# Reefwing-NFC-Card-RevC.net
KiCad netlist of a schematic drawn in EasyEDA
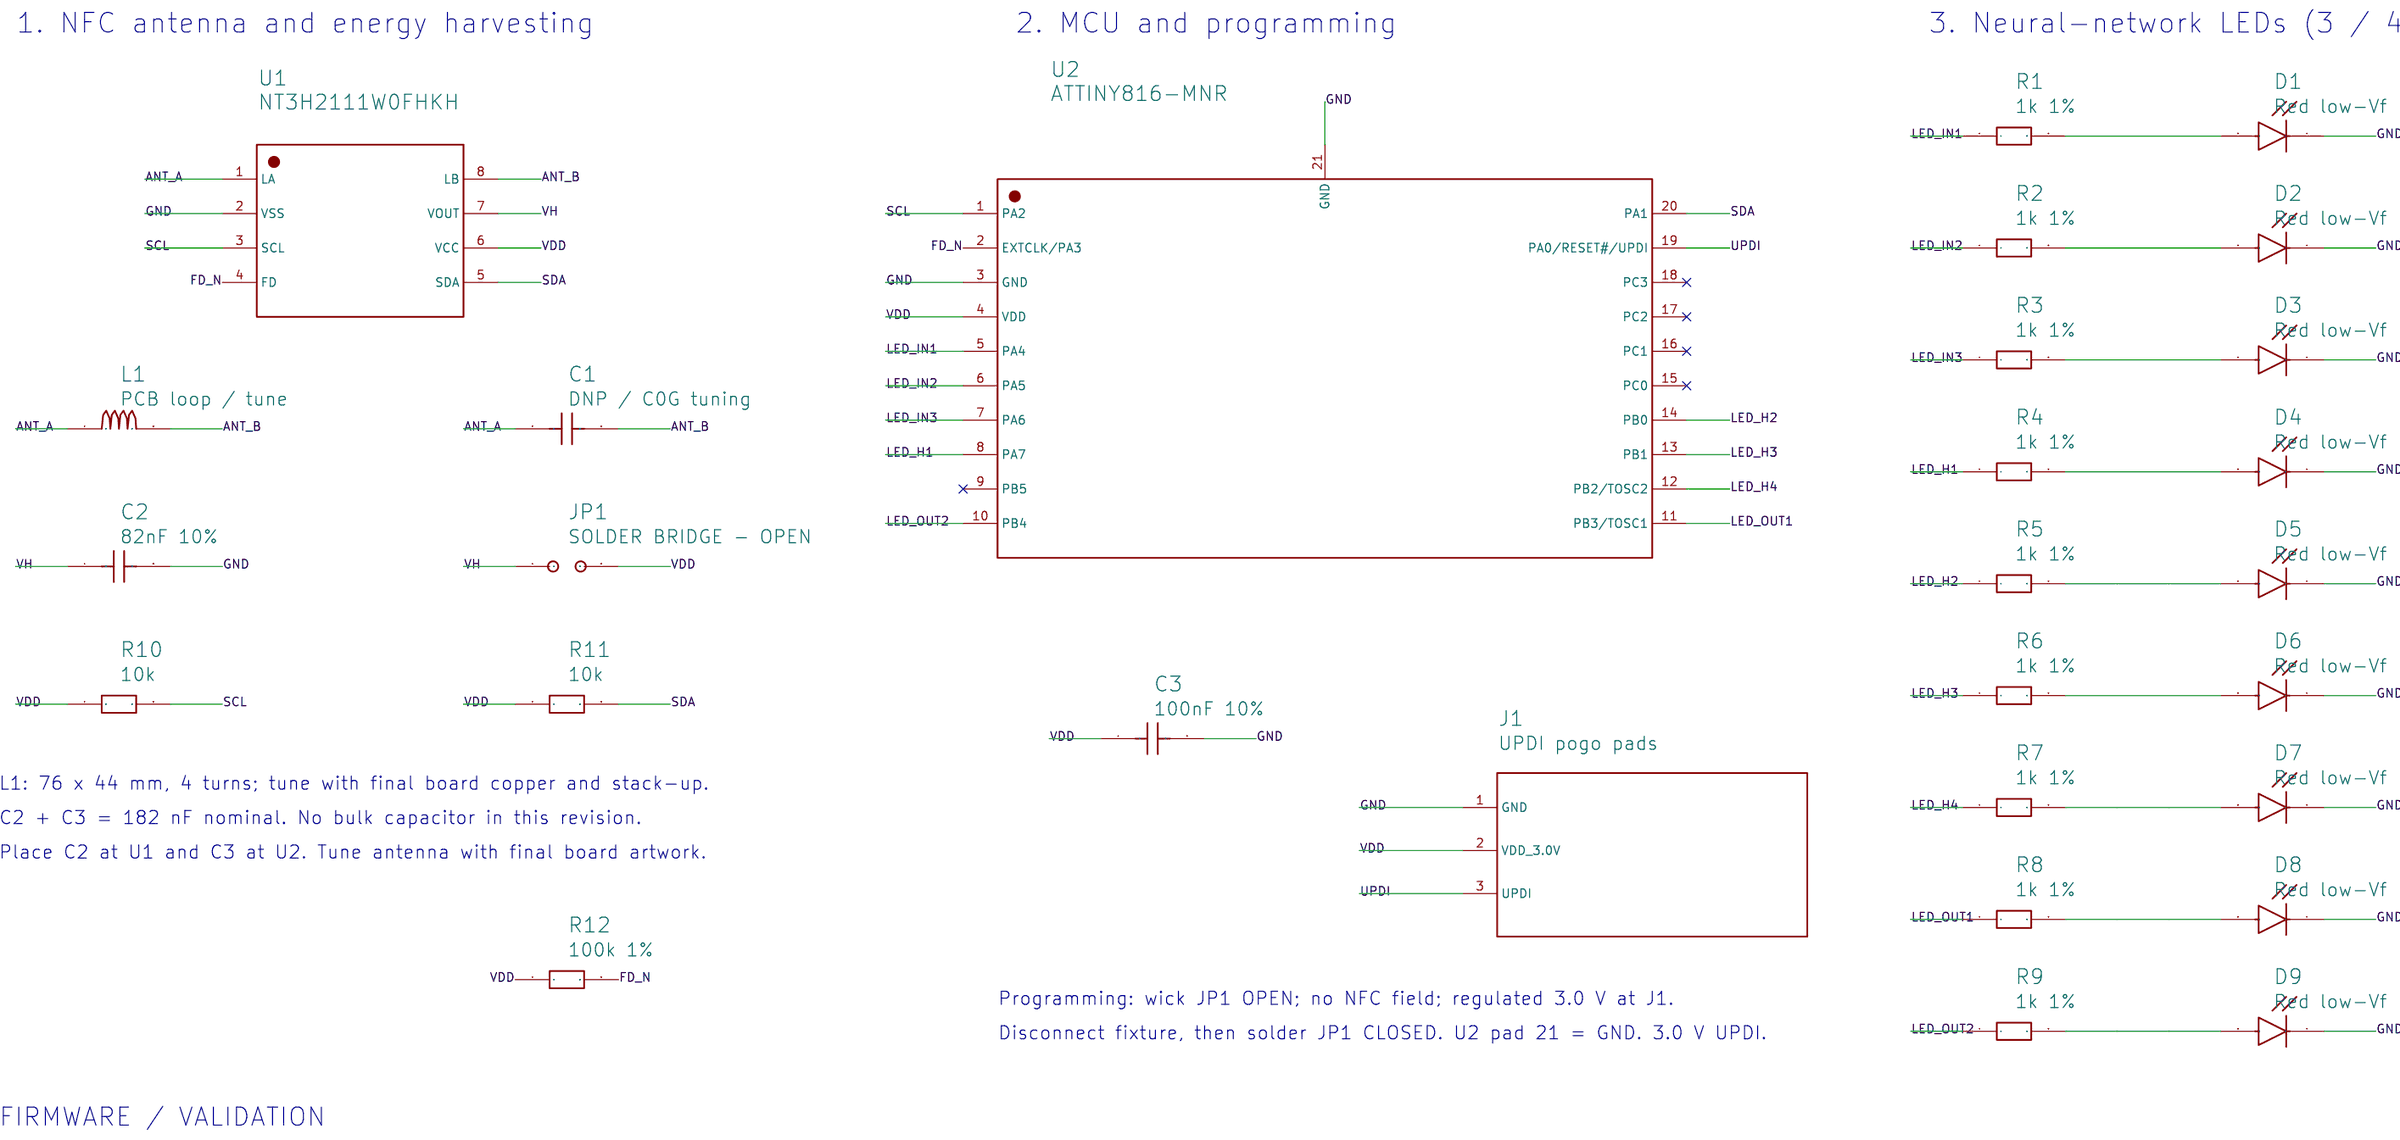
[diagram p0: schematic sheet]

(export (version "E")
  (design (tool "Eeschema 10.0.6"))
  (components
    (comp (ref "C1") (value "DNP / C0G tuning") (libsource (lib "") (part "Unknown_400_365")))
    (comp (ref "C2")
      (value "82nF 10%")
      (fields
        (field (name "Manufacturer Part") "CC0603KRX7R9BB823")
        (field (name "Manufacturer") "YAGEO(国巨)")
        (field (name "BOM_Supplier Part") "C107100")
      )
      (libsource (lib "") (part "Unknown_140_445"))
    )
    (comp (ref "C3")
      (value "100nF 10%")
      (fields
        (field (name "Manufacturer Part") "CC0603KRX7R9BB104")
        (field (name "Manufacturer") "YAGEO(国巨)")
        (field (name "BOM_Supplier Part") "C14663")
      )
      (libsource (lib "") (part "Unknown_740_545"))
    )
    (comp (ref "D1")
      (value "Red low-Vf")
      (fields
        (field (name "Manufacturer Part") "KT-0603R")
        (field (name "Manufacturer") "KENTO")
        (field (name "BOM_Supplier Part") "C2286")
      )
      (libsource (lib "") (part "Unknown_1390_195"))
    )
    (comp (ref "D2")
      (value "Red low-Vf")
      (fields
        (field (name "Manufacturer Part") "KT-0603R")
        (field (name "Manufacturer") "KENTO")
        (field (name "BOM_Supplier Part") "C2286")
      )
      (libsource (lib "") (part "Unknown_1390_260"))
    )
    (comp (ref "D3")
      (value "Red low-Vf")
      (fields
        (field (name "Manufacturer Part") "KT-0603R")
        (field (name "Manufacturer") "KENTO")
        (field (name "BOM_Supplier Part") "C2286")
      )
      (libsource (lib "") (part "Unknown_1390_325"))
    )
    (comp (ref "D4")
      (value "Red low-Vf")
      (fields
        (field (name "Manufacturer Part") "KT-0603R")
        (field (name "Manufacturer") "KENTO")
        (field (name "BOM_Supplier Part") "C2286")
      )
      (libsource (lib "") (part "Unknown_1390_390"))
    )
    (comp (ref "D5")
      (value "Red low-Vf")
      (fields
        (field (name "Manufacturer Part") "KT-0603R")
        (field (name "Manufacturer") "KENTO")
        (field (name "BOM_Supplier Part") "C2286")
      )
      (libsource (lib "") (part "Unknown_1390_455"))
    )
    (comp (ref "D6")
      (value "Red low-Vf")
      (fields
        (field (name "Manufacturer Part") "KT-0603R")
        (field (name "Manufacturer") "KENTO")
        (field (name "BOM_Supplier Part") "C2286")
      )
      (libsource (lib "") (part "Unknown_1390_520"))
    )
    (comp (ref "D7")
      (value "Red low-Vf")
      (fields
        (field (name "Manufacturer Part") "KT-0603R")
        (field (name "Manufacturer") "KENTO")
        (field (name "BOM_Supplier Part") "C2286")
      )
      (libsource (lib "") (part "Unknown_1390_585"))
    )
    (comp (ref "D8")
      (value "Red low-Vf")
      (fields
        (field (name "Manufacturer Part") "KT-0603R")
        (field (name "Manufacturer") "KENTO")
        (field (name "BOM_Supplier Part") "C2286")
      )
      (libsource (lib "") (part "Unknown_1390_650"))
    )
    (comp (ref "D9")
      (value "Red low-Vf")
      (fields
        (field (name "Manufacturer Part") "KT-0603R")
        (field (name "Manufacturer") "KENTO")
        (field (name "BOM_Supplier Part") "C2286")
      )
      (libsource (lib "") (part "Unknown_1390_715"))
    )
    (comp (ref "J1") (value "UPDI pogo pads") (libsource (lib "") (part "Unknown_940_565")))
    (comp (ref "JP1") (value "SOLDER BRIDGE - OPEN") (libsource (lib "") (part "Unknown_400_445")))
    (comp (ref "L1") (value "PCB loop / tune") (libsource (lib "") (part "Unknown_140_365")))
    (comp (ref "R1")
      (value "1k 1%")
      (fields
        (field (name "Manufacturer Part") "0603WAF1001T5E")
        (field (name "Manufacturer") "UNI-ROYAL(厚声)")
        (field (name "BOM_Supplier Part") "C21190")
      )
      (libsource (lib "") (part "Unknown_1240_195"))
    )
    (comp (ref "R2")
      (value "1k 1%")
      (fields
        (field (name "Manufacturer Part") "0603WAF1001T5E")
        (field (name "Manufacturer") "UNI-ROYAL(厚声)")
        (field (name "BOM_Supplier Part") "C21190")
      )
      (libsource (lib "") (part "Unknown_1240_260"))
    )
    (comp (ref "R3")
      (value "1k 1%")
      (fields
        (field (name "Manufacturer Part") "0603WAF1001T5E")
        (field (name "Manufacturer") "UNI-ROYAL(厚声)")
        (field (name "BOM_Supplier Part") "C21190")
      )
      (libsource (lib "") (part "Unknown_1240_325"))
    )
    (comp (ref "R4")
      (value "1k 1%")
      (fields
        (field (name "Manufacturer Part") "0603WAF1001T5E")
        (field (name "Manufacturer") "UNI-ROYAL(厚声)")
        (field (name "BOM_Supplier Part") "C21190")
      )
      (libsource (lib "") (part "Unknown_1240_390"))
    )
    (comp (ref "R5")
      (value "1k 1%")
      (fields
        (field (name "Manufacturer Part") "0603WAF1001T5E")
        (field (name "Manufacturer") "UNI-ROYAL(厚声)")
        (field (name "BOM_Supplier Part") "C21190")
      )
      (libsource (lib "") (part "Unknown_1240_455"))
    )
    (comp (ref "R6")
      (value "1k 1%")
      (fields
        (field (name "Manufacturer Part") "0603WAF1001T5E")
        (field (name "Manufacturer") "UNI-ROYAL(厚声)")
        (field (name "BOM_Supplier Part") "C21190")
      )
      (libsource (lib "") (part "Unknown_1240_520"))
    )
    (comp (ref "R7")
      (value "1k 1%")
      (fields
        (field (name "Manufacturer Part") "0603WAF1001T5E")
        (field (name "Manufacturer") "UNI-ROYAL(厚声)")
        (field (name "BOM_Supplier Part") "C21190")
      )
      (libsource (lib "") (part "Unknown_1240_585"))
    )
    (comp (ref "R8")
      (value "1k 1%")
      (fields
        (field (name "Manufacturer Part") "0603WAF1001T5E")
        (field (name "Manufacturer") "UNI-ROYAL(厚声)")
        (field (name "BOM_Supplier Part") "C21190")
      )
      (libsource (lib "") (part "Unknown_1240_650"))
    )
    (comp (ref "R9")
      (value "1k 1%")
      (fields
        (field (name "Manufacturer Part") "0603WAF1001T5E")
        (field (name "Manufacturer") "UNI-ROYAL(厚声)")
        (field (name "BOM_Supplier Part") "C21190")
      )
      (libsource (lib "") (part "Unknown_1240_715"))
    )
    (comp (ref "R10")
      (value "10k")
      (fields
        (field (name "Manufacturer Part") "0603WAF1002T5E")
        (field (name "Manufacturer") "UNI-ROYAL(厚声)")
        (field (name "BOM_Supplier Part") "C25804")
      )
      (libsource (lib "") (part "Unknown_140_525"))
    )
    (comp (ref "R11")
      (value "10k")
      (fields
        (field (name "Manufacturer Part") "0603WAF1002T5E")
        (field (name "Manufacturer") "UNI-ROYAL(厚声)")
        (field (name "BOM_Supplier Part") "C25804")
      )
      (libsource (lib "") (part "Unknown_400_525"))
    )
    (comp (ref "R12")
      (value "100k 1%")
      (fields
        (field (name "Manufacturer Part") "0603WAF1003T5E")
        (field (name "Manufacturer") "UNI-ROYAL(厚声)")
        (field (name "BOM_Supplier Part") "C25803")
      )
      (libsource (lib "") (part "Unknown_400_685"))
    )
    (comp (ref "U1")
      (value "NT3H2111W0FHKH")
      (fields (field (name "Manufacturer") "NXP(恩智浦)") (field (name "BOM_Supplier Part") "C710403"))
      (libsource (lib "") (part "Unknown_280_250"))
    )
    (comp (ref "U2")
      (value "ATTINY816-MNR")
      (fields (field (name "Manufacturer") "MICROCHIP(美国微芯)") (field (name "BOM_Supplier Part") "C2052778"))
      (libsource (lib "") (part "Unknown_840_330"))
    )
  )
  (nets
    (net (code "1") (name "/ANT_A") (class "Default")
      (node (ref "C1") (pin "1") (pinfunction "1_1") (pintype "unspecified"))
      (node (ref "L1") (pin "1") (pinfunction "1_1") (pintype "unspecified"))
      (node (ref "U1") (pin "1") (pinfunction "LA_1") (pintype "unspecified"))
    )
    (net (code "2") (name "/ANT_B") (class "Default")
      (node (ref "C1") (pin "2") (pinfunction "2_2") (pintype "unspecified"))
      (node (ref "L1") (pin "2") (pinfunction "2_2") (pintype "unspecified"))
      (node (ref "U1") (pin "8") (pinfunction "LB_8") (pintype "unspecified"))
    )
    (net (code "3") (name "/FD_N") (class "Default")
      (node (ref "R12") (pin "2") (pinfunction "2_2") (pintype "unspecified"))
      (node (ref "U1") (pin "4") (pinfunction "FD_4") (pintype "output"))
      (node (ref "U2") (pin "2") (pinfunction "EXTCLK/PA3_2") (pintype "bidirectional"))
    )
    (net (code "4") (name "/GND") (class "Default")
      (node (ref "C2") (pin "2") (pinfunction "2_2") (pintype "unspecified"))
      (node (ref "C3") (pin "2") (pinfunction "2_2") (pintype "unspecified"))
      (node (ref "D1") (pin "1") (pinfunction "K_1") (pintype "unspecified"))
      (node (ref "D2") (pin "1") (pinfunction "K_1") (pintype "unspecified"))
      (node (ref "D3") (pin "1") (pinfunction "K_1") (pintype "unspecified"))
      (node (ref "D4") (pin "1") (pinfunction "K_1") (pintype "unspecified"))
      (node (ref "D5") (pin "1") (pinfunction "K_1") (pintype "unspecified"))
      (node (ref "D6") (pin "1") (pinfunction "K_1") (pintype "unspecified"))
      (node (ref "D7") (pin "1") (pinfunction "K_1") (pintype "unspecified"))
      (node (ref "D8") (pin "1") (pinfunction "K_1") (pintype "unspecified"))
      (node (ref "D9") (pin "1") (pinfunction "K_1") (pintype "unspecified"))
      (node (ref "J1") (pin "1") (pinfunction "GND_1") (pintype "unspecified"))
      (node (ref "U1") (pin "2") (pinfunction "VSS_2") (pintype "passive"))
      (node (ref "U2") (pin "21") (pinfunction "GND_21") (pintype "passive"))
      (node (ref "U2") (pin "3") (pinfunction "GND_3") (pintype "passive"))
    )
    (net (code "5") (name "/LED_H1") (class "Default")
      (node (ref "R4") (pin "1") (pinfunction "1_1") (pintype "unspecified"))
      (node (ref "U2") (pin "8") (pinfunction "PA7_8") (pintype "bidirectional"))
    )
    (net (code "6") (name "/LED_H2") (class "Default")
      (node (ref "R5") (pin "1") (pinfunction "1_1") (pintype "unspecified"))
      (node (ref "U2") (pin "14") (pinfunction "PB0_14") (pintype "bidirectional"))
    )
    (net (code "7") (name "/LED_H3") (class "Default")
      (node (ref "R6") (pin "1") (pinfunction "1_1") (pintype "unspecified"))
      (node (ref "U2") (pin "13") (pinfunction "PB1_13") (pintype "bidirectional"))
    )
    (net (code "8") (name "/LED_H4") (class "Default")
      (node (ref "R7") (pin "1") (pinfunction "1_1") (pintype "unspecified"))
      (node (ref "U2") (pin "12") (pinfunction "PB2/TOSC2_12") (pintype "bidirectional"))
    )
    (net (code "9") (name "/LED_IN1") (class "Default")
      (node (ref "R1") (pin "1") (pinfunction "1_1") (pintype "unspecified"))
      (node (ref "U2") (pin "5") (pinfunction "PA4_5") (pintype "bidirectional"))
    )
    (net (code "10") (name "/LED_IN2") (class "Default")
      (node (ref "R2") (pin "1") (pinfunction "1_1") (pintype "unspecified"))
      (node (ref "U2") (pin "6") (pinfunction "PA5_6") (pintype "bidirectional"))
    )
    (net (code "11") (name "/LED_IN3") (class "Default")
      (node (ref "R3") (pin "1") (pinfunction "1_1") (pintype "unspecified"))
      (node (ref "U2") (pin "7") (pinfunction "PA6_7") (pintype "bidirectional"))
    )
    (net (code "12") (name "/LED_OUT1") (class "Default")
      (node (ref "R8") (pin "1") (pinfunction "1_1") (pintype "unspecified"))
      (node (ref "U2") (pin "11") (pinfunction "PB3/TOSC1_11") (pintype "bidirectional"))
    )
    (net (code "13") (name "/LED_OUT2") (class "Default")
      (node (ref "R9") (pin "1") (pinfunction "1_1") (pintype "unspecified"))
      (node (ref "U2") (pin "10") (pinfunction "PB4_10") (pintype "bidirectional"))
    )
    (net (code "14") (name "/SCL") (class "Default")
      (node (ref "R10") (pin "2") (pinfunction "2_2") (pintype "unspecified"))
      (node (ref "U1") (pin "3") (pinfunction "SCL_3") (pintype "input"))
      (node (ref "U2") (pin "1") (pinfunction "PA2_1") (pintype "bidirectional"))
    )
    (net (code "15") (name "/SDA") (class "Default")
      (node (ref "R11") (pin "2") (pinfunction "2_2") (pintype "unspecified"))
      (node (ref "U1") (pin "5") (pinfunction "SDA_5") (pintype "bidirectional"))
      (node (ref "U2") (pin "20") (pinfunction "PA1_20") (pintype "bidirectional"))
    )
    (net (code "16") (name "/UPDI") (class "Default")
      (node (ref "J1") (pin "3") (pinfunction "UPDI_3") (pintype "unspecified"))
      (node (ref "U2") (pin "19") (pinfunction "PA0/RESET#/UPDI_19") (pintype "bidirectional"))
    )
    (net (code "17") (name "/VDD") (class "Default")
      (node (ref "C3") (pin "1") (pinfunction "1_1") (pintype "unspecified"))
      (node (ref "J1") (pin "2") (pinfunction "VDD_3.0V_2") (pintype "unspecified"))
      (node (ref "JP1") (pin "2") (pinfunction "2_2") (pintype "unspecified"))
      (node (ref "R10") (pin "1") (pinfunction "1_1") (pintype "unspecified"))
      (node (ref "R11") (pin "1") (pinfunction "1_1") (pintype "unspecified"))
      (node (ref "R12") (pin "1") (pinfunction "1_1") (pintype "unspecified"))
      (node (ref "U1") (pin "6") (pinfunction "VCC_6") (pintype "passive"))
      (node (ref "U2") (pin "4") (pinfunction "VDD_4") (pintype "passive"))
    )
    (net (code "18") (name "/VH") (class "Default")
      (node (ref "C2") (pin "1") (pinfunction "1_1") (pintype "unspecified"))
      (node (ref "JP1") (pin "1") (pinfunction "1_1") (pintype "unspecified"))
      (node (ref "U1") (pin "7") (pinfunction "VOUT_7") (pintype "passive"))
    )
    (net (code "19") (name "Net-(D1-A)") (class "Default")
      (node (ref "D1") (pin "2") (pinfunction "A_2") (pintype "unspecified"))
      (node (ref "R1") (pin "2") (pinfunction "2_2") (pintype "unspecified"))
    )
    (net (code "20") (name "Net-(D2-A)") (class "Default")
      (node (ref "D2") (pin "2") (pinfunction "A_2") (pintype "unspecified"))
      (node (ref "R2") (pin "2") (pinfunction "2_2") (pintype "unspecified"))
    )
    (net (code "21") (name "Net-(D3-A)") (class "Default")
      (node (ref "D3") (pin "2") (pinfunction "A_2") (pintype "unspecified"))
      (node (ref "R3") (pin "2") (pinfunction "2_2") (pintype "unspecified"))
    )
    (net (code "22") (name "Net-(D4-A)") (class "Default")
      (node (ref "D4") (pin "2") (pinfunction "A_2") (pintype "unspecified"))
      (node (ref "R4") (pin "2") (pinfunction "2_2") (pintype "unspecified"))
    )
    (net (code "23") (name "Net-(D5-A)") (class "Default")
      (node (ref "D5") (pin "2") (pinfunction "A_2") (pintype "unspecified"))
      (node (ref "R5") (pin "2") (pinfunction "2_2") (pintype "unspecified"))
    )
    (net (code "24") (name "Net-(D6-A)") (class "Default")
      (node (ref "D6") (pin "2") (pinfunction "A_2") (pintype "unspecified"))
      (node (ref "R6") (pin "2") (pinfunction "2_2") (pintype "unspecified"))
    )
    (net (code "25") (name "Net-(D7-A)") (class "Default")
      (node (ref "D7") (pin "2") (pinfunction "A_2") (pintype "unspecified"))
      (node (ref "R7") (pin "2") (pinfunction "2_2") (pintype "unspecified"))
    )
    (net (code "26") (name "Net-(D8-A)") (class "Default")
      (node (ref "D8") (pin "2") (pinfunction "A_2") (pintype "unspecified"))
      (node (ref "R8") (pin "2") (pinfunction "2_2") (pintype "unspecified"))
    )
    (net (code "27") (name "Net-(D9-A)") (class "Default")
      (node (ref "D9") (pin "2") (pinfunction "A_2") (pintype "unspecified"))
      (node (ref "R9") (pin "2") (pinfunction "2_2") (pintype "unspecified"))
    )
    (net (code "28") (name "unconnected-(U2-PB5-Pad9)") (class "Default")
      (node (ref "U2") (pin "9") (pinfunction "PB5_9") (pintype "bidirectional+no_connect"))
    )
    (net (code "29") (name "unconnected-(U2-PC0-Pad15)") (class "Default")
      (node (ref "U2") (pin "15") (pinfunction "PC0_15") (pintype "bidirectional+no_connect"))
    )
    (net (code "30") (name "unconnected-(U2-PC1-Pad16)") (class "Default")
      (node (ref "U2") (pin "16") (pinfunction "PC1_16") (pintype "bidirectional+no_connect"))
    )
    (net (code "31") (name "unconnected-(U2-PC2-Pad17)") (class "Default")
      (node (ref "U2") (pin "17") (pinfunction "PC2_17") (pintype "bidirectional+no_connect"))
    )
    (net (code "32") (name "unconnected-(U2-PC3-Pad18)") (class "Default")
      (node (ref "U2") (pin "18") (pinfunction "PC3_18") (pintype "bidirectional+no_connect"))
    )
  )
)
